# LevelShifter.net
KiCad netlist of a schematic drawn in Altium Designer
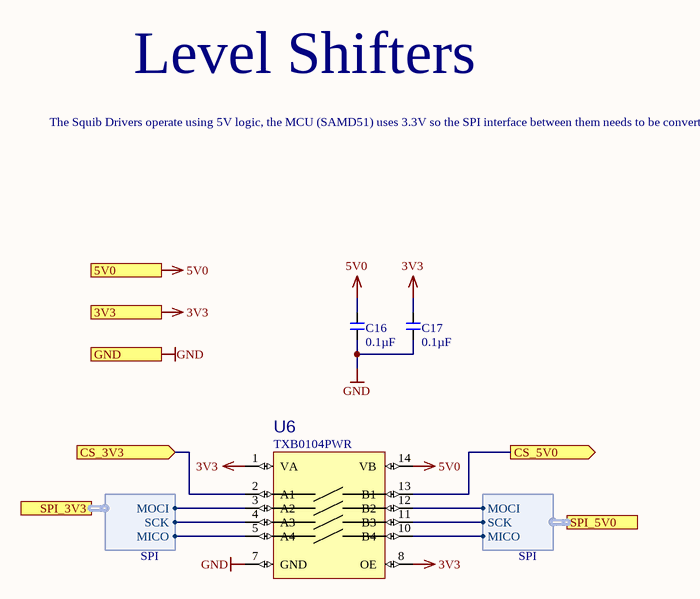
[diagram p0: LevelShifter.SchDoc]

(export (version "E")
  (design (tool "Eeschema 10.0.6"))
  (components
    (comp (ref "C16")
      (value "490-1519-1-ND")
      (footprint "C0603")
      (description "CAP CER 0603 0.1µF X7R 50V 10%")
      (fields
        (field (name "CAPACITANCE (SHORTHAND)") "0.1µF")
        (field (name "MANUFACTURER") "Murata Electronics North America")
      )
      (libsource (lib "Stanford Student Space Initiative") (part "__template_cap"))
    )
    (comp (ref "C17")
      (value "490-1519-1-ND")
      (footprint "C0603")
      (description "CAP CER 0603 0.1µF X7R 50V 10%")
      (fields
        (field (name "CAPACITANCE (SHORTHAND)") "0.1µF")
        (field (name "MANUFACTURER") "Murata Electronics North America")
      )
      (libsource (lib "Stanford Student Space Initiative") (part "__template_cap"))
    )
    (comp (ref "U6")
      (value "LVLSHFT_TXB0104PWR")
      (footprint "14TSSOP65")
      (description "4 Pin Bidirectional levelshifter 5v-3.3v")
      (fields
        (field (name "MANUFACTURER") "Texas Instruments")
        (field (name "MANUFACTURER PART NUMBER") "TXB0104PWR")
      )
      (libsource (lib "Stanford Student Space Initiative") (part "LVLSHFT_TXB0104PWR"))
    )
  )
  (nets
    (net (code "2") (name "/CS_3V3") (class "Default")
      (node (ref "U6") (pin "2") (pinfunction "A1_2") (pintype "bidirectional"))
    )
    (net (code "3") (name "/CS_5V0") (class "Default")
      (node (ref "U6") (pin "13") (pinfunction "B1_13") (pintype "bidirectional"))
    )
    (net (code "5") (name "3V3") (class "Default")
      (node (ref "C17") (pin "1") (pintype "passive"))
      (node (ref "U6") (pin "1") (pinfunction "VA_1") (pintype "bidirectional"))
      (node (ref "U6") (pin "8") (pinfunction "OE_8") (pintype "bidirectional"))
    )
    (net (code "6") (name "5V0") (class "Default")
      (node (ref "C16") (pin "1") (pintype "passive"))
      (node (ref "U6") (pin "14") (pinfunction "VB_14") (pintype "bidirectional"))
    )
    (net (code "7") (name "GND") (class "Default")
      (node (ref "C16") (pin "2") (pintype "passive"))
      (node (ref "C17") (pin "2") (pintype "passive"))
      (node (ref "U6") (pin "7") (pinfunction "GND_7") (pintype "bidirectional"))
    )
    (net (code "8") (name "unconnected-(U6-A2-Pad3)") (class "Default")
      (node (ref "U6") (pin "3") (pinfunction "A2_3") (pintype "bidirectional"))
    )
    (net (code "9") (name "unconnected-(U6-A3-Pad4)") (class "Default")
      (node (ref "U6") (pin "4") (pinfunction "A3_4") (pintype "bidirectional"))
    )
    (net (code "10") (name "unconnected-(U6-A4-Pad5)") (class "Default")
      (node (ref "U6") (pin "5") (pinfunction "A4_5") (pintype "bidirectional"))
    )
    (net (code "11") (name "unconnected-(U6-B2-Pad12)") (class "Default")
      (node (ref "U6") (pin "12") (pinfunction "B2_12") (pintype "bidirectional"))
    )
    (net (code "12") (name "unconnected-(U6-B3-Pad11)") (class "Default")
      (node (ref "U6") (pin "11") (pinfunction "B3_11") (pintype "bidirectional"))
    )
    (net (code "13") (name "unconnected-(U6-B4-Pad10)") (class "Default")
      (node (ref "U6") (pin "10") (pinfunction "B4_10") (pintype "bidirectional"))
    )
  )
)
